# H-Bridge.net
KiCad netlist of a schematic drawn in EAGLE
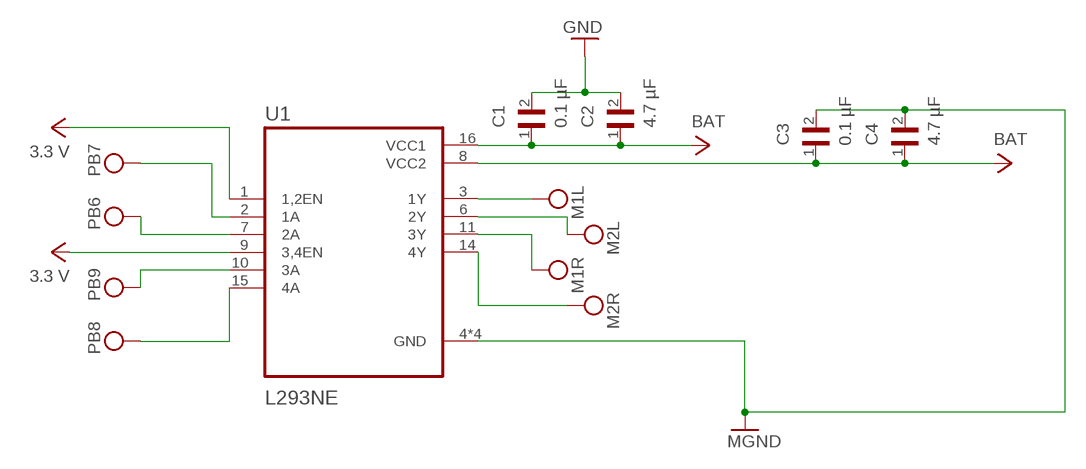
[diagram p0: schematic, sheet 1]

(export (version "E")
  (design (tool "Eeschema 10.0.6"))
  (components
    (comp (ref "C1")
      (value "0.1 µF")
      (footprint "eagle-import:CAPC2012X140N")
      (fields
        (field (name "DIGI-KEY_PART_NUMBER") "490-10516-1-ND")
        (field (name "MF") "Murata Electronics")
        (field (name "MP") "GRM21BR71A106KA73L")
      )
      (libsource (lib "eagle-import") (part "GRM21BR71A106KA73L"))
    )
    (comp (ref "C2")
      (value "4.7 µF")
      (footprint "eagle-import:CAPC2012X140N")
      (fields
        (field (name "DIGI-KEY_PART_NUMBER") "490-10516-1-ND")
        (field (name "MF") "Murata Electronics")
        (field (name "MP") "GRM21BR71A106KA73L")
      )
      (libsource (lib "eagle-import") (part "GRM21BR71A106KA73L"))
    )
    (comp (ref "C3")
      (value "0.1 µF")
      (footprint "eagle-import:CAPC2012X140N")
      (fields
        (field (name "DIGI-KEY_PART_NUMBER") "490-10516-1-ND")
        (field (name "MF") "Murata Electronics")
        (field (name "MP") "GRM21BR71A106KA73L")
      )
      (libsource (lib "eagle-import") (part "GRM21BR71A106KA73L"))
    )
    (comp (ref "C4")
      (value "4.7 µF")
      (footprint "eagle-import:CAPC2012X140N")
      (fields
        (field (name "DIGI-KEY_PART_NUMBER") "490-10516-1-ND")
        (field (name "MF") "Murata Electronics")
        (field (name "MP") "GRM21BR71A106KA73L")
      )
      (libsource (lib "eagle-import") (part "GRM21BR71A106KA73L"))
    )
    (comp (ref "U1")
      (value "L293NE")
      (footprint "eagle-import:DIP762W45P254L1980H508Q16")
      (fields (field (name "MF") "Texas Instruments"))
      (libsource (lib "eagle-import") (part "L293NE"))
    )
  )
  (nets
    (net (code "1") (name "3.3 V") (class "Default")
      (node (ref "C1") (pin "1") (pinfunction "1_1") (pintype "passive"))
      (node (ref "C2") (pin "1") (pinfunction "1_1") (pintype "passive"))
      (node (ref "C3") (pin "1") (pinfunction "1_1") (pintype "passive"))
      (node (ref "C4") (pin "1") (pinfunction "1_1") (pintype "passive"))
      (node (ref "U1") (pin "1") (pinfunction "1,2EN_1") (pintype "input"))
      (node (ref "U1") (pin "10") (pinfunction "3A_10") (pintype "input"))
      (node (ref "U1") (pin "11") (pinfunction "3Y_11") (pintype "output"))
      (node (ref "U1") (pin "14") (pinfunction "4Y_14") (pintype "output"))
      (node (ref "U1") (pin "15") (pinfunction "4A_15") (pintype "input"))
      (node (ref "U1") (pin "16") (pinfunction "VCC1_16") (pintype "power_in"))
      (node (ref "U1") (pin "2") (pinfunction "1A_2") (pintype "input"))
      (node (ref "U1") (pin "3") (pinfunction "1Y_3") (pintype "output"))
      (node (ref "U1") (pin "6") (pinfunction "2Y_6") (pintype "output"))
      (node (ref "U1") (pin "7") (pinfunction "2A_7") (pintype "input"))
      (node (ref "U1") (pin "8") (pinfunction "VCC2_8") (pintype "power_in"))
      (node (ref "U1") (pin "9") (pinfunction "3,4EN_9") (pintype "input"))
    )
    (net (code "2") (name "GND") (class "Default")
      (node (ref "C1") (pin "2") (pinfunction "2_2") (pintype "passive"))
      (node (ref "C2") (pin "2") (pinfunction "2_2") (pintype "passive"))
      (node (ref "C3") (pin "2") (pinfunction "2_2") (pintype "passive"))
      (node (ref "C4") (pin "2") (pinfunction "2_2") (pintype "passive"))
      (node (ref "U1") (pin "12") (pinfunction "GND_12") (pintype "power_in"))
      (node (ref "U1") (pin "13") (pinfunction "GND_13") (pintype "power_in"))
      (node (ref "U1") (pin "4") (pinfunction "GND_4") (pintype "power_in"))
      (node (ref "U1") (pin "5") (pinfunction "GND_5") (pintype "power_in"))
    )
  )
)
